# magnetorquer_board_f1.net
KiCad netlist of a schematic drawn in EAGLE
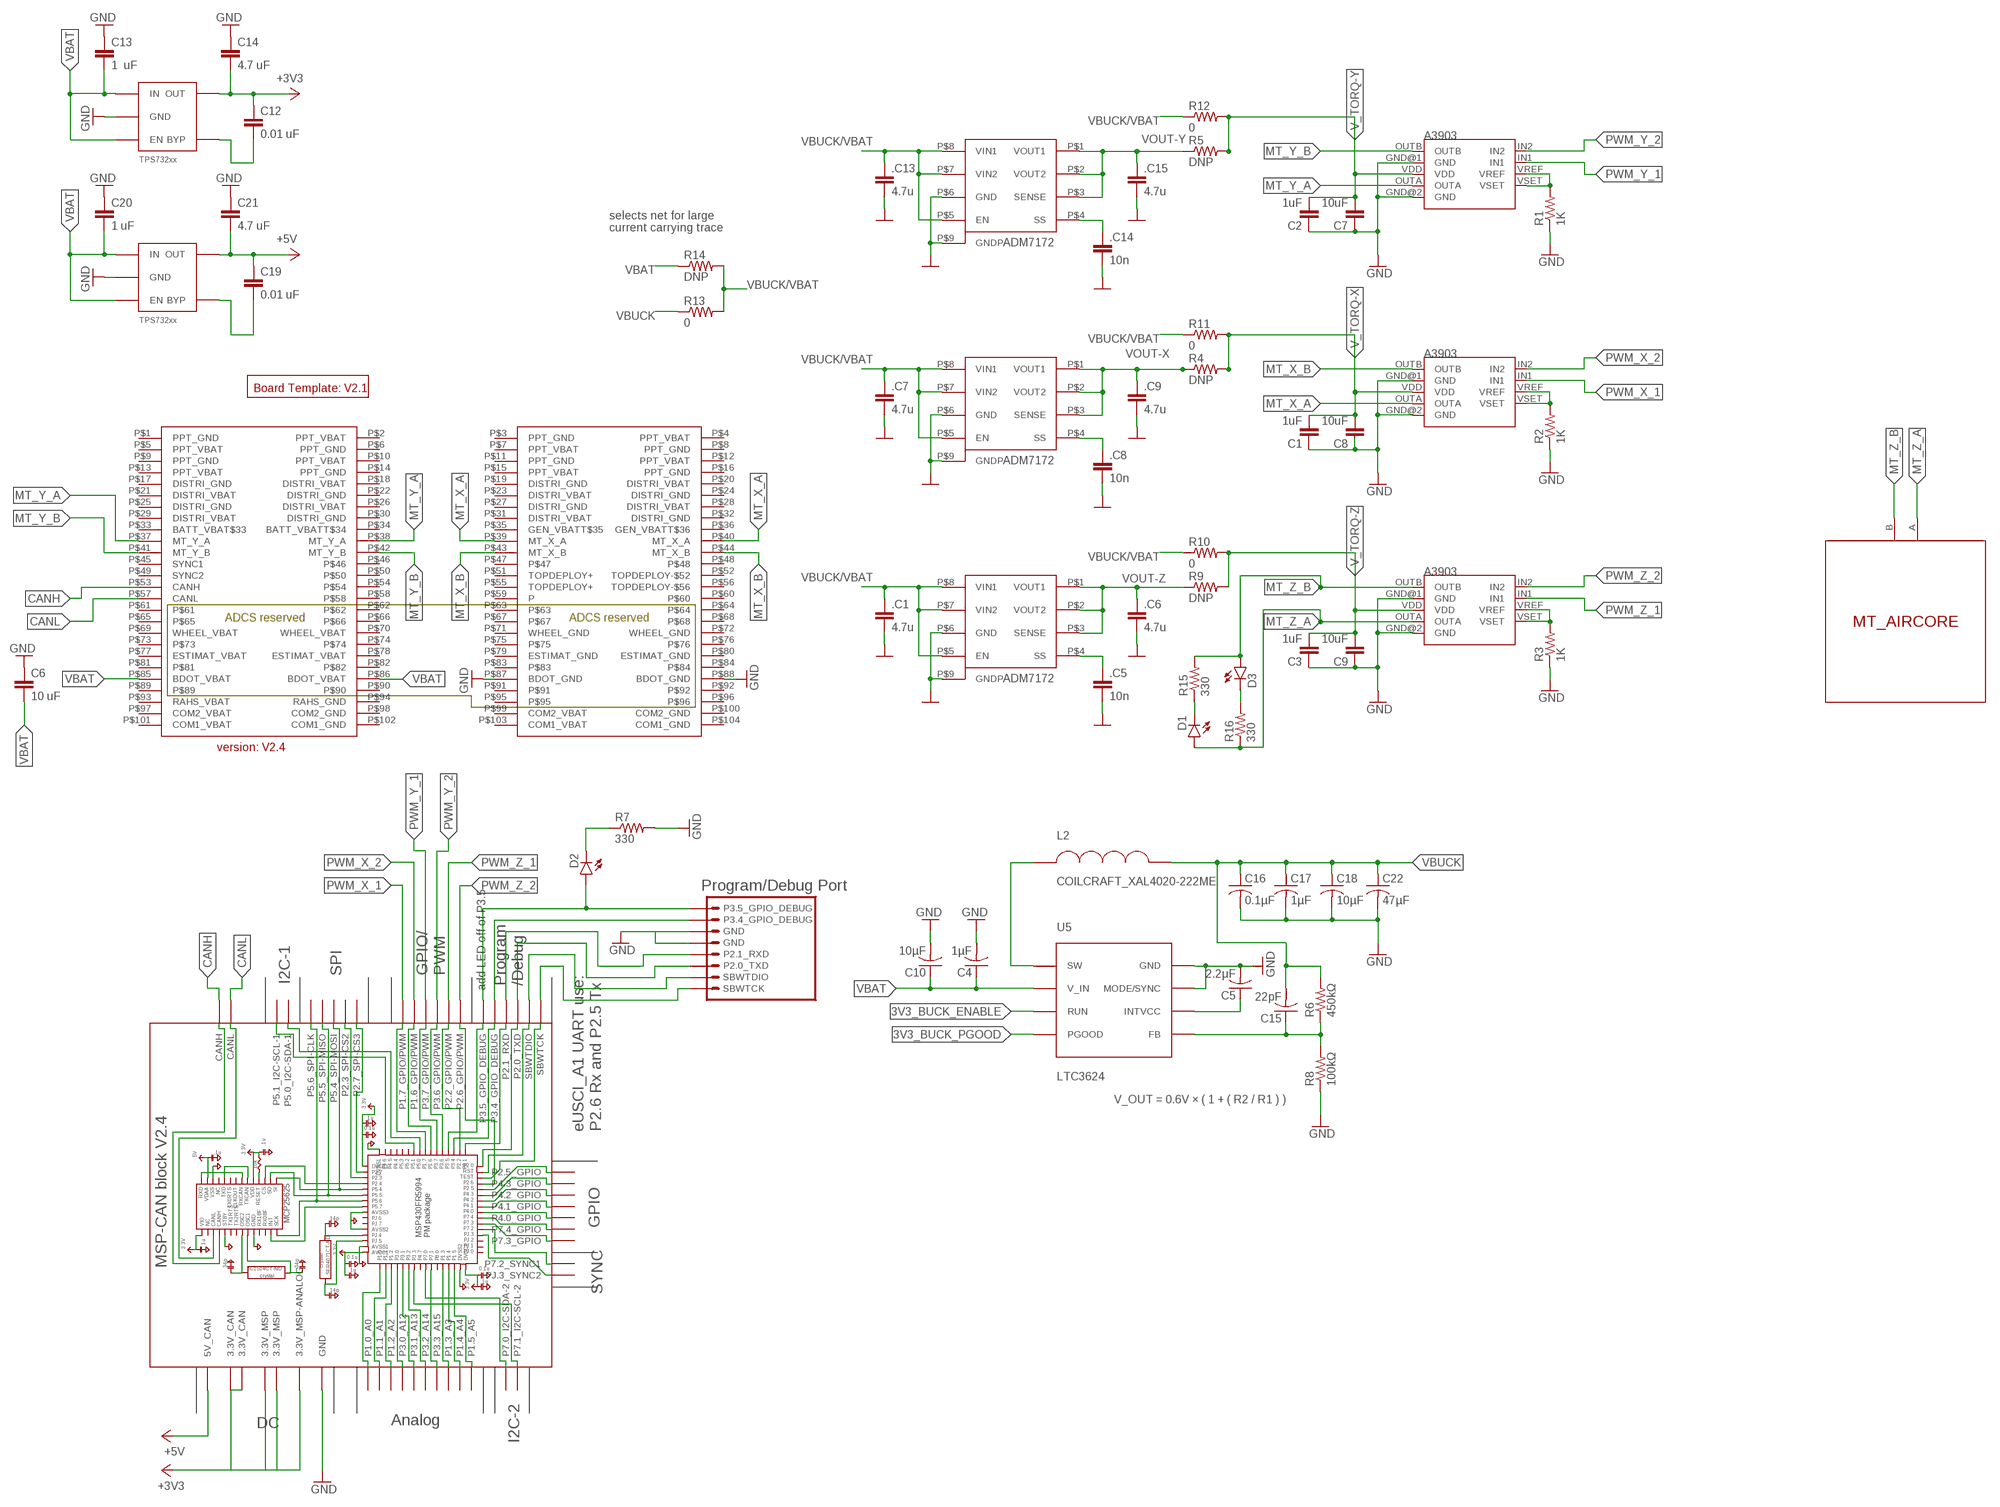
[diagram p0: schematic, sheet 1]

(export (version "E")
  (design (tool "Eeschema 10.0.6"))
  (components
    (comp (ref ".C1")
      (value "4.7u")
      (footprint "eagle-import:1206")
      (libsource (lib "eagle-import") (part "CAP1206"))
    )
    (comp (ref ".C5")
      (value "10n")
      (footprint "eagle-import:0805")
      (libsource (lib "eagle-import") (part "CAP0805"))
    )
    (comp (ref ".C6")
      (value "4.7u")
      (footprint "eagle-import:1206")
      (libsource (lib "eagle-import") (part "CAP1206"))
    )
    (comp (ref ".C7")
      (value "4.7u")
      (footprint "eagle-import:1206")
      (libsource (lib "eagle-import") (part "CAP1206"))
    )
    (comp (ref ".C8")
      (value "10n")
      (footprint "eagle-import:0805")
      (libsource (lib "eagle-import") (part "CAP0805"))
    )
    (comp (ref ".C9")
      (value "4.7u")
      (footprint "eagle-import:1206")
      (libsource (lib "eagle-import") (part "CAP1206"))
    )
    (comp (ref ".C13")
      (value "4.7u")
      (footprint "eagle-import:1206")
      (libsource (lib "eagle-import") (part "CAP1206"))
    )
    (comp (ref ".C14")
      (value "10n")
      (footprint "eagle-import:0805")
      (libsource (lib "eagle-import") (part "CAP0805"))
    )
    (comp (ref ".C15")
      (value "4.7u")
      (footprint "eagle-import:1206")
      (libsource (lib "eagle-import") (part "CAP1206"))
    )
    (comp (ref "C1")
      (value "1uF")
      (footprint "eagle-import:0805")
      (libsource (lib "eagle-import") (part "CAPACITOR0805"))
    )
    (comp (ref "C2")
      (value "1uF")
      (footprint "eagle-import:0805")
      (libsource (lib "eagle-import") (part "CAPACITOR0805"))
    )
    (comp (ref "C3")
      (value "1uF")
      (footprint "eagle-import:0805")
      (libsource (lib "eagle-import") (part "CAPACITOR0805"))
    )
    (comp (ref "C4")
      (value "1µF")
      (footprint "eagle-import:C0805")
      (libsource (lib "eagle-import") (part "C-USC0805"))
    )
    (comp (ref "C5")
      (value "2.2μF")
      (footprint "eagle-import:C0805")
      (libsource (lib "eagle-import") (part "C-USC0805"))
    )
    (comp (ref "C6")
      (value "10 uF")
      (footprint "eagle-import:0805")
      (libsource (lib "eagle-import") (part "CAPACITOR0805"))
    )
    (comp (ref "C7")
      (value "10uF")
      (footprint "eagle-import:0805")
      (libsource (lib "eagle-import") (part "CAPACITOR0805"))
    )
    (comp (ref "C8")
      (value "10uF")
      (footprint "eagle-import:0805")
      (libsource (lib "eagle-import") (part "CAPACITOR0805"))
    )
    (comp (ref "C9")
      (value "10uF")
      (footprint "eagle-import:0805")
      (libsource (lib "eagle-import") (part "CAPACITOR0805"))
    )
    (comp (ref "C10")
      (value "10µF")
      (footprint "eagle-import:C0805")
      (libsource (lib "eagle-import") (part "C-USC0805"))
    )
    (comp (ref "C12")
      (value "0.01 uF")
      (footprint "eagle-import:0805")
      (libsource (lib "eagle-import") (part "CAPACITOR0805"))
    )
    (comp (ref "C13")
      (value "1 uF")
      (footprint "eagle-import:0805")
      (libsource (lib "eagle-import") (part "CAPACITOR0805"))
    )
    (comp (ref "C14")
      (value "4.7 uF")
      (footprint "eagle-import:0805")
      (libsource (lib "eagle-import") (part "CAPACITOR0805"))
    )
    (comp (ref "C15")
      (value "22pF")
      (footprint "eagle-import:C0805")
      (libsource (lib "eagle-import") (part "C-USC0805"))
    )
    (comp (ref "C16")
      (value "0.1µF")
      (footprint "eagle-import:C1206")
      (libsource (lib "eagle-import") (part "C-USC1206"))
    )
    (comp (ref "C17")
      (value "1µF")
      (footprint "eagle-import:C0805")
      (libsource (lib "eagle-import") (part "C-USC0805"))
    )
    (comp (ref "C18")
      (value "10µF")
      (footprint "eagle-import:C0805")
      (libsource (lib "eagle-import") (part "C-USC0805"))
    )
    (comp (ref "C19")
      (value "0.01 uF")
      (footprint "eagle-import:0805")
      (libsource (lib "eagle-import") (part "CAPACITOR0805"))
    )
    (comp (ref "C20")
      (value "1 uF")
      (footprint "eagle-import:0805")
      (libsource (lib "eagle-import") (part "CAPACITOR0805"))
    )
    (comp (ref "C21")
      (value "4.7 uF")
      (footprint "eagle-import:0805")
      (libsource (lib "eagle-import") (part "CAPACITOR0805"))
    )
    (comp (ref "C22")
      (value "47µF")
      (footprint "eagle-import:C0805")
      (libsource (lib "eagle-import") (part "C-USC0805"))
    )
    (comp (ref "D1")
      (value "LED")
      (footprint "eagle-import:LED-1206")
      (libsource (lib "eagle-import") (part "LED"))
    )
    (comp (ref "D2")
      (value "LED")
      (footprint "eagle-import:LED-1206")
      (libsource (lib "eagle-import") (part "LED"))
    )
    (comp (ref "D3")
      (value "LED")
      (footprint "eagle-import:LED-1206")
      (libsource (lib "eagle-import") (part "LED"))
    )
    (comp (ref "L2")
      (value "COILCRAFT_XAL4020-222ME")
      (footprint "eagle-import:COILCRAFT_XAL4020")
      (libsource (lib "eagle-import") (part "COILCRAFT_XAL4020-222ME"))
    )
    (comp (ref "LDO_3V1")
      (value "TPS732XX")
      (footprint "eagle-import:SOT-23-5")
      (libsource (lib "eagle-import") (part "TPS732XX"))
    )
    (comp (ref "LDO_5V1")
      (value "TPS732XX")
      (footprint "eagle-import:SOT-23-5")
      (libsource (lib "eagle-import") (part "TPS732XX"))
    )
    (comp (ref "R1")
      (value "1K")
      (footprint "eagle-import:R0603")
      (libsource (lib "eagle-import") (part "R-US_R0603"))
    )
    (comp (ref "R2")
      (value "1K")
      (footprint "eagle-import:R0603")
      (libsource (lib "eagle-import") (part "R-US_R0603"))
    )
    (comp (ref "R3")
      (value "1K")
      (footprint "eagle-import:R0603")
      (libsource (lib "eagle-import") (part "R-US_R0603"))
    )
    (comp (ref "R4")
      (value "DNP")
      (footprint "eagle-import:0805")
      (libsource (lib "eagle-import") (part "RESISTOR0805"))
    )
    (comp (ref "R5")
      (value "DNP")
      (footprint "eagle-import:0805")
      (libsource (lib "eagle-import") (part "RESISTOR0805"))
    )
    (comp (ref "R6")
      (value "450kΩ")
      (footprint "eagle-import:R0805")
      (libsource (lib "eagle-import") (part "R-US_R0805"))
    )
    (comp (ref "R7")
      (value "330")
      (footprint "eagle-import:0805")
      (libsource (lib "eagle-import") (part "RESISTOR0805"))
    )
    (comp (ref "R8")
      (value "100kΩ")
      (footprint "eagle-import:R0805")
      (libsource (lib "eagle-import") (part "R-US_R0805"))
    )
    (comp (ref "R9")
      (value "DNP")
      (footprint "eagle-import:0805")
      (libsource (lib "eagle-import") (part "RESISTOR0805"))
    )
    (comp (ref "R10")
      (value "0")
      (footprint "eagle-import:0805")
      (libsource (lib "eagle-import") (part "RESISTOR0805"))
    )
    (comp (ref "R11")
      (value "0")
      (footprint "eagle-import:0805")
      (libsource (lib "eagle-import") (part "RESISTOR0805"))
    )
    (comp (ref "R12")
      (value "0")
      (footprint "eagle-import:0805")
      (libsource (lib "eagle-import") (part "RESISTOR0805"))
    )
    (comp (ref "R13")
      (value "0")
      (footprint "eagle-import:R2010")
      (libsource (lib "eagle-import") (part "RESISTOR2010"))
    )
    (comp (ref "R14")
      (value "DNP")
      (footprint "eagle-import:R2010")
      (libsource (lib "eagle-import") (part "RESISTOR2010"))
    )
    (comp (ref "R15")
      (value "330")
      (footprint "eagle-import:0805")
      (libsource (lib "eagle-import") (part "RESISTOR0805"))
    )
    (comp (ref "R16")
      (value "330")
      (footprint "eagle-import:0805")
      (libsource (lib "eagle-import") (part "RESISTOR0805"))
    )
    (comp (ref "U$1")
      (value "PC104_CONNECTOR")
      (footprint "eagle-import:PC104_CONNECTOR")
      (libsource (lib "eagle-import") (part "PC104_CONNECTOR"))
    )
    (comp (ref "U$2")
      (value "BOARD_TEMPLATE1")
      (footprint "eagle-import:BOARD_TEMPLATE")
      (libsource (lib "eagle-import") (part "BOARD_TEMPLATE1"))
    )
    (comp (ref "U$3")
      (value "MT_AIRCORE")
      (footprint "eagle-import:MT_AIRCORE")
      (libsource (lib "eagle-import") (part "MT_AIRCORE"))
    )
    (comp (ref "U$4")
      (value "ANALOG_LDO_ADM7172")
      (footprint "eagle-import:8-LFCSP")
      (libsource (lib "eagle-import") (part "ANALOG_LDO_ADM7172"))
    )
    (comp (ref "U$5")
      (value "ANALOG_LDO_ADM7172")
      (footprint "eagle-import:8-LFCSP")
      (libsource (lib "eagle-import") (part "ANALOG_LDO_ADM7172"))
    )
    (comp (ref "U$7")
      (value "MSP-CAN_BLOCK")
      (footprint "eagle-import:MSP-CAN_BLOCK")
      (libsource (lib "eagle-import") (part "MSP-CAN_BLOCK"))
    )
    (comp (ref "U$8")
      (value "PROGRAM/DEBUG_PORT")
      (footprint "eagle-import:1X08_CONNECTOR")
      (libsource (lib "eagle-import") (part "PROGRAM/DEBUG_PORT"))
    )
    (comp (ref "U$9")
      (value "ANALOG_LDO_ADM7172")
      (footprint "eagle-import:8-LFCSP")
      (libsource (lib "eagle-import") (part "ANALOG_LDO_ADM7172"))
    )
    (comp (ref "U1")
      (value "A3903")
      (footprint "eagle-import:DFN-8EE")
      (libsource (lib "eagle-import") (part "A3903"))
    )
    (comp (ref "U2")
      (value "A3903")
      (footprint "eagle-import:DFN-8EE")
      (libsource (lib "eagle-import") (part "A3903"))
    )
    (comp (ref "U3")
      (value "A3903")
      (footprint "eagle-import:DFN-8EE")
      (libsource (lib "eagle-import") (part "A3903"))
    )
    (comp (ref "U5")
      (value "LTC3624")
      (footprint "eagle-import:LTC3624")
      (libsource (lib "eagle-import") (part "LTC3624"))
    )
  )
  (nets
    (net (code "1") (name "+3V3") (class "Default")
      (node (ref "C12") (pin "1") (pinfunction "1_1") (pintype "passive"))
      (node (ref "C14") (pin "2") (pinfunction "2_2") (pintype "passive"))
      (node (ref "LDO_3V1") (pin "P$5") (pinfunction "OUT_P$5") (pintype "bidirectional"))
      (node (ref "U$7") (pin "3.3V@CAN1") (pinfunction "3.3V_CAN_3.3V@CAN1") (pintype "bidirectional"))
      (node (ref "U$7") (pin "3.3V@CAN2") (pinfunction "3.3V_CAN_3.3V@CAN2") (pintype "bidirectional"))
      (node (ref "U$7") (pin "3.3V@MSP1") (pinfunction "3.3V_MSP_3.3V@MSP1") (pintype "bidirectional"))
      (node (ref "U$7") (pin "3.3V@MSP2") (pinfunction "3.3V_MSP_3.3V@MSP2") (pintype "bidirectional"))
      (node (ref "U$7") (pin "3.3V_ANALOG@MSP2") (pinfunction "3.3V_MSP-ANALOG_3.3V_ANALOG@MSP2") (pintype "bidirectional"))
    )
    (net (code "2") (name "+5V") (class "Default")
      (node (ref "C19") (pin "1") (pinfunction "1_1") (pintype "passive"))
      (node (ref "C21") (pin "2") (pinfunction "2_2") (pintype "passive"))
      (node (ref "LDO_5V1") (pin "P$5") (pinfunction "OUT_P$5") (pintype "bidirectional"))
      (node (ref "U$7") (pin "5V") (pinfunction "5V_CAN_5V") (pintype "bidirectional"))
    )
    (net (code "3") (name "/VBUCK{slash}VBAT") (class "Default")
      (node (ref ".C1") (pin "1") (pinfunction "1_1") (pintype "passive"))
      (node (ref ".C13") (pin "1") (pinfunction "1_1") (pintype "passive"))
      (node (ref ".C7") (pin "1") (pinfunction "1_1") (pintype "passive"))
      (node (ref "R10") (pin "1") (pinfunction "1_1") (pintype "passive"))
      (node (ref "R11") (pin "1") (pinfunction "1_1") (pintype "passive"))
      (node (ref "R12") (pin "1") (pinfunction "1_1") (pintype "passive"))
      (node (ref "R13") (pin "2") (pinfunction "2_2") (pintype "passive"))
      (node (ref "R14") (pin "2") (pinfunction "2_2") (pintype "passive"))
      (node (ref "U$4") (pin "P$5") (pinfunction "EN_P$5") (pintype "bidirectional"))
      (node (ref "U$4") (pin "P$7") (pinfunction "VIN2_P$7") (pintype "bidirectional"))
      (node (ref "U$4") (pin "P$8") (pinfunction "VIN1_P$8") (pintype "bidirectional"))
      (node (ref "U$5") (pin "P$5") (pinfunction "EN_P$5") (pintype "bidirectional"))
      (node (ref "U$5") (pin "P$7") (pinfunction "VIN2_P$7") (pintype "bidirectional"))
      (node (ref "U$5") (pin "P$8") (pinfunction "VIN1_P$8") (pintype "bidirectional"))
      (node (ref "U$9") (pin "P$5") (pinfunction "EN_P$5") (pintype "bidirectional"))
      (node (ref "U$9") (pin "P$7") (pinfunction "VIN2_P$7") (pintype "bidirectional"))
      (node (ref "U$9") (pin "P$8") (pinfunction "VIN1_P$8") (pintype "bidirectional"))
    )
    (net (code "4") (name "/VOUT-X") (class "Default")
      (node (ref ".C9") (pin "1") (pinfunction "1_1") (pintype "passive"))
      (node (ref "R4") (pin "1") (pinfunction "1_1") (pintype "passive"))
      (node (ref "U$5") (pin "P$1") (pinfunction "VOUT1_P$1") (pintype "bidirectional"))
      (node (ref "U$5") (pin "P$2") (pinfunction "VOUT2_P$2") (pintype "bidirectional"))
      (node (ref "U$5") (pin "P$3") (pinfunction "SENSE_P$3") (pintype "bidirectional"))
    )
    (net (code "5") (name "/VOUT-Y") (class "Default")
      (node (ref ".C15") (pin "1") (pinfunction "1_1") (pintype "passive"))
      (node (ref "R5") (pin "1") (pinfunction "1_1") (pintype "passive"))
      (node (ref "U$9") (pin "P$1") (pinfunction "VOUT1_P$1") (pintype "bidirectional"))
      (node (ref "U$9") (pin "P$2") (pinfunction "VOUT2_P$2") (pintype "bidirectional"))
      (node (ref "U$9") (pin "P$3") (pinfunction "SENSE_P$3") (pintype "bidirectional"))
    )
    (net (code "6") (name "/VOUT-Z") (class "Default")
      (node (ref ".C6") (pin "1") (pinfunction "1_1") (pintype "passive"))
      (node (ref "R9") (pin "1") (pinfunction "1_1") (pintype "passive"))
      (node (ref "U$4") (pin "P$1") (pinfunction "VOUT1_P$1") (pintype "bidirectional"))
      (node (ref "U$4") (pin "P$2") (pinfunction "VOUT2_P$2") (pintype "bidirectional"))
      (node (ref "U$4") (pin "P$3") (pinfunction "SENSE_P$3") (pintype "bidirectional"))
    )
    (net (code "7") (name "3V3_BUCK_ENABLE") (class "Default")
      (node (ref "U5") (pin "RUN") (pinfunction "RUN_RUN") (pintype "bidirectional"))
    )
    (net (code "8") (name "3V3_BUCK_PGOOD") (class "Default")
      (node (ref "U5") (pin "PGOOD") (pinfunction "PGOOD_PGOOD") (pintype "bidirectional"))
    )
    (net (code "9") (name "CANH") (class "Default")
      (node (ref "U$1") (pin "P$53") (pinfunction "CANH_P$53") (pintype "bidirectional"))
      (node (ref "U$7") (pin "CANH") (pinfunction "CANH_CANH") (pintype "bidirectional"))
    )
    (net (code "10") (name "CANL") (class "Default")
      (node (ref "U$1") (pin "P$57") (pinfunction "CANL_P$57") (pintype "bidirectional"))
      (node (ref "U$7") (pin "CANL") (pinfunction "CANL_CANL") (pintype "bidirectional"))
    )
    (net (code "11") (name "DGND") (class "Default")
      (node (ref ".C1") (pin "2") (pinfunction "2_2") (pintype "passive"))
      (node (ref ".C13") (pin "2") (pinfunction "2_2") (pintype "passive"))
      (node (ref ".C14") (pin "2") (pinfunction "2_2") (pintype "passive"))
      (node (ref ".C15") (pin "2") (pinfunction "2_2") (pintype "passive"))
      (node (ref ".C5") (pin "2") (pinfunction "2_2") (pintype "passive"))
      (node (ref ".C6") (pin "2") (pinfunction "2_2") (pintype "passive"))
      (node (ref ".C7") (pin "2") (pinfunction "2_2") (pintype "passive"))
      (node (ref ".C8") (pin "2") (pinfunction "2_2") (pintype "passive"))
      (node (ref ".C9") (pin "2") (pinfunction "2_2") (pintype "passive"))
      (node (ref "C1") (pin "1") (pinfunction "1_1") (pintype "passive"))
      (node (ref "C10") (pin "2") (pinfunction "2_2") (pintype "passive"))
      (node (ref "C13") (pin "1") (pinfunction "1_1") (pintype "passive"))
      (node (ref "C14") (pin "1") (pinfunction "1_1") (pintype "passive"))
      (node (ref "C16") (pin "2") (pinfunction "2_2") (pintype "passive"))
      (node (ref "C17") (pin "2") (pinfunction "2_2") (pintype "passive"))
      (node (ref "C18") (pin "2") (pinfunction "2_2") (pintype "passive"))
      (node (ref "C2") (pin "1") (pinfunction "1_1") (pintype "passive"))
      (node (ref "C20") (pin "1") (pinfunction "1_1") (pintype "passive"))
      (node (ref "C21") (pin "1") (pinfunction "1_1") (pintype "passive"))
      (node (ref "C22") (pin "2") (pinfunction "2_2") (pintype "passive"))
      (node (ref "C3") (pin "1") (pinfunction "1_1") (pintype "passive"))
      (node (ref "C4") (pin "2") (pinfunction "2_2") (pintype "passive"))
      (node (ref "C5") (pin "2") (pinfunction "2_2") (pintype "passive"))
      (node (ref "C6") (pin "1") (pinfunction "1_1") (pintype "passive"))
      (node (ref "C7") (pin "1") (pinfunction "1_1") (pintype "passive"))
      (node (ref "C8") (pin "1") (pinfunction "1_1") (pintype "passive"))
      (node (ref "C9") (pin "1") (pinfunction "1_1") (pintype "passive"))
      (node (ref "LDO_3V1") (pin "P$2") (pinfunction "GND_P$2") (pintype "bidirectional"))
      (node (ref "LDO_5V1") (pin "P$2") (pinfunction "GND_P$2") (pintype "bidirectional"))
      (node (ref "R1") (pin "1") (pinfunction "1_1") (pintype "passive"))
      (node (ref "R2") (pin "1") (pinfunction "1_1") (pintype "passive"))
      (node (ref "R3") (pin "1") (pinfunction "1_1") (pintype "passive"))
      (node (ref "R7") (pin "2") (pinfunction "2_2") (pintype "passive"))
      (node (ref "R8") (pin "1") (pinfunction "1_1") (pintype "passive"))
      (node (ref "U$1") (pin "P$87") (pinfunction "BDOT_GND_P$87") (pintype "bidirectional"))
      (node (ref "U$1") (pin "P$88") (pinfunction "BDOT_GND_P$88") (pintype "bidirectional"))
      (node (ref "U$4") (pin "P$6") (pinfunction "GND_P$6") (pintype "bidirectional"))
      (node (ref "U$4") (pin "P$9") (pinfunction "GNDP_P$9") (pintype "bidirectional"))
      (node (ref "U$5") (pin "P$6") (pinfunction "GND_P$6") (pintype "bidirectional"))
      (node (ref "U$5") (pin "P$9") (pinfunction "GNDP_P$9") (pintype "bidirectional"))
      (node (ref "U$7") (pin "GND@1") (pinfunction "GND_GND@1") (pintype "bidirectional"))
      (node (ref "U$7") (pin "GND@10") (pinfunction "GND_GND@10") (pintype "bidirectional"))
      (node (ref "U$7") (pin "GND@11") (pinfunction "GND_GND@11") (pintype "bidirectional"))
      (node (ref "U$7") (pin "GND@12") (pinfunction "GND_GND@12") (pintype "bidirectional"))
      (node (ref "U$7") (pin "GND@13") (pinfunction "GND_GND@13") (pintype "bidirectional"))
      (node (ref "U$7") (pin "GND@14") (pinfunction "GND_GND@14") (pintype "bidirectional"))
      (node (ref "U$7") (pin "GND@15") (pinfunction "GND_GND@15") (pintype "bidirectional"))
      (node (ref "U$7") (pin "GND@16") (pinfunction "GND_GND@16") (pintype "bidirectional"))
      (node (ref "U$7") (pin "GND@17") (pinfunction "GND_GND@17") (pintype "bidirectional"))
      (node (ref "U$7") (pin "GND@2") (pinfunction "GND_GND@2") (pintype "bidirectional"))
      (node (ref "U$7") (pin "GND@26") (pinfunction "GND_GND@26") (pintype "bidirectional"))
      (node (ref "U$7") (pin "GND@3") (pinfunction "GND_GND@3") (pintype "bidirectional"))
      (node (ref "U$7") (pin "GND@4") (pinfunction "GND_GND@4") (pintype "bidirectional"))
      (node (ref "U$7") (pin "GND@5") (pinfunction "GND_GND@5") (pintype "bidirectional"))
      (node (ref "U$7") (pin "GND@7") (pinfunction "GND_GND@7") (pintype "bidirectional"))
      (node (ref "U$7") (pin "GND@8") (pinfunction "GND_GND@8") (pintype "bidirectional"))
      (node (ref "U$7") (pin "GND@9") (pinfunction "GND_GND@9") (pintype "bidirectional"))
      (node (ref "U$8") (pin "5") (pinfunction "GND_5") (pintype "bidirectional"))
      (node (ref "U$8") (pin "6") (pinfunction "GND_6") (pintype "bidirectional"))
      (node (ref "U$9") (pin "P$6") (pinfunction "GND_P$6") (pintype "bidirectional"))
      (node (ref "U$9") (pin "P$9") (pinfunction "GNDP_P$9") (pintype "bidirectional"))
      (node (ref "U1") (pin "GND@1") (pinfunction "GND_GND@1") (pintype "power_in"))
      (node (ref "U1") (pin "GND@2") (pinfunction "GND_GND@2") (pintype "power_in"))
      (node (ref "U2") (pin "GND@1") (pinfunction "GND_GND@1") (pintype "power_in"))
      (node (ref "U2") (pin "GND@2") (pinfunction "GND_GND@2") (pintype "power_in"))
      (node (ref "U3") (pin "GND@1") (pinfunction "GND_GND@1") (pintype "power_in"))
      (node (ref "U3") (pin "GND@2") (pinfunction "GND_GND@2") (pintype "power_in"))
      (node (ref "U5") (pin "GND@1") (pinfunction "GND_GND@1") (pintype "bidirectional"))
      (node (ref "U5") (pin "GND@PAD") (pinfunction "GND_GND@PAD") (pintype "bidirectional"))
      (node (ref "U5") (pin "MODE/SYNC") (pinfunction "MODE/SYNC_MODE/SYNC") (pintype "bidirectional"))
    )
    (net (code "12") (name "MT_X_A") (class "Default")
      (node (ref "U$1") (pin "P$39") (pinfunction "MT_X_A_P$39") (pintype "bidirectional"))
      (node (ref "U$1") (pin "P$40") (pinfunction "MT_X_A_P$40") (pintype "bidirectional"))
      (node (ref "U2") (pin "OUTA") (pinfunction "OUTA_OUTA") (pintype "output"))
    )
    (net (code "13") (name "MT_X_B") (class "Default")
      (node (ref "U$1") (pin "P$43") (pinfunction "MT_X_B_P$43") (pintype "bidirectional"))
      (node (ref "U$1") (pin "P$44") (pinfunction "MT_X_B_P$44") (pintype "bidirectional"))
      (node (ref "U2") (pin "OUTB") (pinfunction "OUTB_OUTB") (pintype "output"))
    )
    (net (code "14") (name "MT_Y_A") (class "Default")
      (node (ref "U$1") (pin "P$37") (pinfunction "MT_Y_A_P$37") (pintype "bidirectional"))
      (node (ref "U$1") (pin "P$38") (pinfunction "MT_Y_A_P$38") (pintype "bidirectional"))
      (node (ref "U1") (pin "OUTA") (pinfunction "OUTA_OUTA") (pintype "output"))
    )
    (net (code "15") (name "MT_Y_B") (class "Default")
      (node (ref "U$1") (pin "P$41") (pinfunction "MT_Y_B_P$41") (pintype "bidirectional"))
      (node (ref "U$1") (pin "P$42") (pinfunction "MT_Y_B_P$42") (pintype "bidirectional"))
      (node (ref "U1") (pin "OUTB") (pinfunction "OUTB_OUTB") (pintype "output"))
    )
    (net (code "16") (name "MT_Z_A") (class "Default")
      (node (ref "D1") (pin "A") (pinfunction "A_A") (pintype "passive"))
      (node (ref "R16") (pin "1") (pinfunction "1_1") (pintype "passive"))
      (node (ref "U$3") (pin "A") (pinfunction "A_A") (pintype "bidirectional"))
      (node (ref "U3") (pin "OUTA") (pinfunction "OUTA_OUTA") (pintype "output"))
    )
    (net (code "17") (name "MT_Z_B") (class "Default")
      (node (ref "D3") (pin "A") (pinfunction "A_A") (pintype "passive"))
      (node (ref "R15") (pin "2") (pinfunction "2_2") (pintype "passive"))
      (node (ref "U$3") (pin "B") (pinfunction "B_B") (pintype "bidirectional"))
      (node (ref "U3") (pin "OUTB") (pinfunction "OUTB_OUTB") (pintype "output"))
    )
    (net (code "18") (name "Net-(C5-Pad1)") (class "Default")
      (node (ref "C5") (pin "1") (pinfunction "1_1") (pintype "passive"))
      (node (ref "U5") (pin "INTVCC") (pinfunction "INTVCC_INTVCC") (pintype "bidirectional"))
    )
    (net (code "19") (name "Net-(C15-Pad1)") (class "Default")
      (node (ref "C15") (pin "1") (pinfunction "1_1") (pintype "passive"))
      (node (ref "R6") (pin "1") (pinfunction "1_1") (pintype "passive"))
      (node (ref "R8") (pin "2") (pinfunction "2_2") (pintype "passive"))
      (node (ref "U5") (pin "FB") (pinfunction "FB_FB") (pintype "bidirectional"))
    )
    (net (code "20") (name "Net-(D1-PadC)") (class "Default")
      (node (ref "D1") (pin "C") (pinfunction "C_C") (pintype "passive"))
      (node (ref "R15") (pin "1") (pinfunction "1_1") (pintype "passive"))
    )
    (net (code "21") (name "Net-(D2-PadC)") (class "Default")
      (node (ref "D2") (pin "C") (pinfunction "C_C") (pintype "passive"))
      (node (ref "R7") (pin "1") (pinfunction "1_1") (pintype "passive"))
    )
    (net (code "22") (name "Net-(D3-PadC)") (class "Default")
      (node (ref "D3") (pin "C") (pinfunction "C_C") (pintype "passive"))
      (node (ref "R16") (pin "2") (pinfunction "2_2") (pintype "passive"))
    )
    (net (code "23") (name "Net-(L2-PadP$1)") (class "Default")
      (node (ref "L2") (pin "P$1") (pinfunction "P$1_P$1") (pintype "bidirectional"))
      (node (ref "U5") (pin "SW") (pinfunction "SW_SW") (pintype "bidirectional"))
    )
    (net (code "24") (name "Net-(LDO_3V1-BYP)") (class "Default")
      (node (ref "C12") (pin "2") (pinfunction "2_2") (pintype "passive"))
      (node (ref "LDO_3V1") (pin "P$4") (pinfunction "BYP_P$4") (pintype "bidirectional"))
    )
    (net (code "25") (name "Net-(LDO_5V1-BYP)") (class "Default")
      (node (ref "C19") (pin "2") (pinfunction "2_2") (pintype "passive"))
      (node (ref "LDO_5V1") (pin "P$4") (pinfunction "BYP_P$4") (pintype "bidirectional"))
    )
    (net (code "26") (name "Net-(R1-Pad2)") (class "Default")
      (node (ref "R1") (pin "2") (pinfunction "2_2") (pintype "passive"))
      (node (ref "U1") (pin "VREF") (pinfunction "VREF_VREF") (pintype "power_in"))
      (node (ref "U1") (pin "VSET") (pinfunction "VSET_VSET") (pintype "bidirectional"))
    )
    (net (code "27") (name "Net-(R2-Pad2)") (class "Default")
      (node (ref "R2") (pin "2") (pinfunction "2_2") (pintype "passive"))
      (node (ref "U2") (pin "VREF") (pinfunction "VREF_VREF") (pintype "power_in"))
      (node (ref "U2") (pin "VSET") (pinfunction "VSET_VSET") (pintype "bidirectional"))
    )
    (net (code "28") (name "Net-(R3-Pad2)") (class "Default")
      (node (ref "R3") (pin "2") (pinfunction "2_2") (pintype "passive"))
      (node (ref "U3") (pin "VREF") (pinfunction "VREF_VREF") (pintype "power_in"))
      (node (ref "U3") (pin "VSET") (pinfunction "VSET_VSET") (pintype "bidirectional"))
    )
    (net (code "29") (name "Net-(U$4-SS)") (class "Default")
      (node (ref ".C5") (pin "1") (pinfunction "1_1") (pintype "passive"))
      (node (ref "U$4") (pin "P$4") (pinfunction "SS_P$4") (pintype "bidirectional"))
    )
    (net (code "30") (name "Net-(U$5-SS)") (class "Default")
      (node (ref ".C8") (pin "1") (pinfunction "1_1") (pintype "passive"))
      (node (ref "U$5") (pin "P$4") (pinfunction "SS_P$4") (pintype "bidirectional"))
    )
    (net (code "31") (name "Net-(U$7-PadSBWTCK)") (class "Default")
      (node (ref "U$7") (pin "SBWTCK") (pinfunction "SBWTCK_SBWTCK") (pintype "bidirectional"))
      (node (ref "U$8") (pin "SBWTCK") (pinfunction "SBWTCK_SBWTCK") (pintype "bidirectional"))
    )
    (net (code "32") (name "Net-(U$8-P2.0_TXD)") (class "Default")
      (node (ref "U$7") (pin "P2.0_TXD") (pinfunction "P2.0_TXD_P2.0_TXD") (pintype "bidirectional"))
      (node (ref "U$8") (pin "3") (pinfunction "P2.0_TXD_3") (pintype "bidirectional"))
    )
    (net (code "33") (name "Net-(U$8-P2.1_RXD)") (class "Default")
      (node (ref "U$7") (pin "P2.1_RXD") (pinfunction "P2.1_RXD_P2.1_RXD") (pintype "bidirectional"))
      (node (ref "U$8") (pin "4") (pinfunction "P2.1_RXD_4") (pintype "bidirectional"))
    )
    (net (code "34") (name "Net-(U$8-P3.4_GPIO_DEBUG)") (class "Default")
      (node (ref "U$7") (pin "P3.4_GPIO_DEBUG") (pinfunction "P3.4_GPIO_DEBUG_P3.4_GPIO_DEBUG") (pintype "bidirectional"))
      (node (ref "U$8") (pin "7") (pinfunction "P3.4_GPIO_DEBUG_7") (pintype "bidirectional"))
    )
    (net (code "35") (name "Net-(U$8-P3.5_GPIO_DEBUG)") (class "Default")
      (node (ref "D2") (pin "A") (pinfunction "A_A") (pintype "passive"))
      (node (ref "U$7") (pin "P3.5_GPIO_DEBUG") (pinfunction "P3.5_GPIO_DEBUG_P3.5_GPIO_DEBUG") (pintype "bidirectional"))
      (node (ref "U$8") (pin "8") (pinfunction "P3.5_GPIO_DEBUG_8") (pintype "bidirectional"))
    )
    (net (code "36") (name "Net-(U$8-SBWTDIO)") (class "Default")
      (node (ref "U$7") (pin "SBWTDIO") (pinfunction "SBWTDIO_SBWTDIO") (pintype "bidirectional"))
      (node (ref "U$8") (pin "2") (pinfunction "SBWTDIO_2") (pintype "bidirectional"))
    )
    (net (code "37") (name "Net-(U$9-SS)") (class "Default")
      (node (ref ".C14") (pin "1") (pinfunction "1_1") (pintype "passive"))
      (node (ref "U$9") (pin "P$4") (pinfunction "SS_P$4") (pintype "bidirectional"))
    )
    (net (code "38") (name "PWM_X_1") (class "Default")
      (node (ref "U$7") (pin "P1.7_GPIO/PWM") (pinfunction "P1.7_GPIO/PWM_P1.7_GPIO/PWM") (pintype "bidirectional"))
      (node (ref "U2") (pin "IN1") (pinfunction "IN1_IN1") (pintype "input"))
    )
    (net (code "39") (name "PWM_X_2") (class "Default")
      (node (ref "U$7") (pin "P1.6_GPIO/PWM") (pinfunction "P1.6_GPIO/PWM_P1.6_GPIO/PWM") (pintype "bidirectional"))
      (node (ref "U2") (pin "IN2") (pinfunction "IN2_IN2") (pintype "input"))
    )
    (net (code "40") (name "PWM_Y_1") (class "Default")
      (node (ref "U$7") (pin "P3.7_GPIO/PWM") (pinfunction "P3.7_GPIO/PWM_P3.7_GPIO/PWM") (pintype "bidirectional"))
      (node (ref "U1") (pin "IN1") (pinfunction "IN1_IN1") (pintype "input"))
    )
    (net (code "41") (name "PWM_Y_2") (class "Default")
      (node (ref "U$7") (pin "P3.6_GPIO/PWM") (pinfunction "P3.6_GPIO/PWM_P3.6_GPIO/PWM") (pintype "bidirectional"))
      (node (ref "U1") (pin "IN2") (pinfunction "IN2_IN2") (pintype "input"))
    )
    (net (code "42") (name "PWM_Z_1") (class "Default")
      (node (ref "U$7") (pin "P2.2_GPIO/PWM") (pinfunction "P2.2_GPIO/PWM_P2.2_GPIO/PWM") (pintype "bidirectional"))
      (node (ref "U3") (pin "IN1") (pinfunction "IN1_IN1") (pintype "input"))
    )
    (net (code "43") (name "PWM_Z_2") (class "Default")
      (node (ref "U$7") (pin "P2.6_GPIO/PWM") (pinfunction "P2.6_GPIO/PWM_P2.6_GPIO/PWM") (pintype "bidirectional"))
      (node (ref "U3") (pin "IN2") (pinfunction "IN2_IN2") (pintype "input"))
    )
    (net (code "44") (name "VBAT") (class "Default")
      (node (ref "C10") (pin "1") (pinfunction "1_1") (pintype "passive"))
      (node (ref "C13") (pin "2") (pinfunction "2_2") (pintype "passive"))
      (node (ref "C20") (pin "2") (pinfunction "2_2") (pintype "passive"))
      (node (ref "C4") (pin "1") (pinfunction "1_1") (pintype "passive"))
      (node (ref "C6") (pin "2") (pinfunction "2_2") (pintype "passive"))
      (node (ref "LDO_3V1") (pin "P$1") (pinfunction "IN_P$1") (pintype "bidirectional"))
      (node (ref "LDO_3V1") (pin "P$3") (pinfunction "EN_P$3") (pintype "bidirectional"))
      (node (ref "LDO_5V1") (pin "P$1") (pinfunction "IN_P$1") (pintype "bidirectional"))
      (node (ref "LDO_5V1") (pin "P$3") (pinfunction "EN_P$3") (pintype "bidirectional"))
      (node (ref "R14") (pin "1") (pinfunction "1_1") (pintype "passive"))
      (node (ref "U$1") (pin "P$85") (pinfunction "BDOT_VBAT_P$85") (pintype "bidirectional"))
      (node (ref "U$1") (pin "P$86") (pinfunction "BDOT_VBAT_P$86") (pintype "bidirectional"))
      (node (ref "U5") (pin "V_IN") (pinfunction "V_IN_V_IN") (pintype "bidirectional"))
    )
    (net (code "45") (name "VBUCK") (class "Default")
      (node (ref "C15") (pin "2") (pinfunction "2_2") (pintype "passive"))
      (node (ref "C16") (pin "1") (pinfunction "1_1") (pintype "passive"))
      (node (ref "C17") (pin "1") (pinfunction "1_1") (pintype "passive"))
      (node (ref "C18") (pin "1") (pinfunction "1_1") (pintype "passive"))
      (node (ref "C22") (pin "1") (pinfunction "1_1") (pintype "passive"))
      (node (ref "L2") (pin "P$2") (pinfunction "P$2_P$2") (pintype "bidirectional"))
      (node (ref "R13") (pin "1") (pinfunction "1_1") (pintype "passive"))
      (node (ref "R6") (pin "2") (pinfunction "2_2") (pintype "passive"))
    )
    (net (code "46") (name "V_TORQ-X") (class "Default")
      (node (ref "C1") (pin "2") (pinfunction "2_2") (pintype "passive"))
      (node (ref "C8") (pin "2") (pinfunction "2_2") (pintype "passive"))
      (node (ref "R11") (pin "2") (pinfunction "2_2") (pintype "passive"))
      (node (ref "R4") (pin "2") (pinfunction "2_2") (pintype "passive"))
      (node (ref "U2") (pin "VDD") (pinfunction "VDD_VDD") (pintype "power_in"))
    )
    (net (code "47") (name "V_TORQ-Y") (class "Default")
      (node (ref "C2") (pin "2") (pinfunction "2_2") (pintype "passive"))
      (node (ref "C7") (pin "2") (pinfunction "2_2") (pintype "passive"))
      (node (ref "R12") (pin "2") (pinfunction "2_2") (pintype "passive"))
      (node (ref "R5") (pin "2") (pinfunction "2_2") (pintype "passive"))
      (node (ref "U1") (pin "VDD") (pinfunction "VDD_VDD") (pintype "power_in"))
    )
    (net (code "48") (name "V_TORQ-Z") (class "Default")
      (node (ref "C3") (pin "2") (pinfunction "2_2") (pintype "passive"))
      (node (ref "C9") (pin "2") (pinfunction "2_2") (pintype "passive"))
      (node (ref "R10") (pin "2") (pinfunction "2_2") (pintype "passive"))
      (node (ref "R9") (pin "2") (pinfunction "2_2") (pintype "passive"))
      (node (ref "U3") (pin "VDD") (pinfunction "VDD_VDD") (pintype "power_in"))
    )
    (net (code "49") (name "unconnected-(U$1-BATT_VBAT$33-PadP$33)") (class "Default")
      (node (ref "U$1") (pin "P$33") (pinfunction "BATT_VBAT$33_P$33") (pintype "bidirectional"))
    )
    (net (code "50") (name "unconnected-(U$1-BATT_VBATT$34-PadP$34)") (class "Default")
      (node (ref "U$1") (pin "P$34") (pinfunction "BATT_VBATT$34_P$34") (pintype "bidirectional"))
    )
    (net (code "51") (name "unconnected-(U$1-COM1_GND-PadP$102)") (class "Default")
      (node (ref "U$1") (pin "P$102") (pinfunction "COM1_GND_P$102") (pintype "bidirectional"))
    )
    (net (code "52") (name "unconnected-(U$1-COM1_GND-PadP$104)") (class "Default")
      (node (ref "U$1") (pin "P$104") (pinfunction "COM1_GND_P$104") (pintype "bidirectional"))
    )
    (net (code "53") (name "unconnected-(U$1-COM1_VBAT-PadP$101)") (class "Default")
      (node (ref "U$1") (pin "P$101") (pinfunction "COM1_VBAT_P$101") (pintype "bidirectional"))
    )
    (net (code "54") (name "unconnected-(U$1-COM1_VBAT-PadP$103)") (class "Default")
      (node (ref "U$1") (pin "P$103") (pinfunction "COM1_VBAT_P$103") (pintype "bidirectional"))
    )
    (net (code "55") (name "unconnected-(U$1-COM2_GND-PadP$98)") (class "Default")
      (node (ref "U$1") (pin "P$98") (pinfunction "COM2_GND_P$98") (pintype "bidirectional"))
    )
    (net (code "56") (name "unconnected-(U$1-COM2_GND-PadP$100)") (class "Default")
      (node (ref "U$1") (pin "P$100") (pinfunction "COM2_GND_P$100") (pintype "bidirectional"))
    )
    (net (code "57") (name "unconnected-(U$1-COM2_VBAT-PadP$97)") (class "Default")
      (node (ref "U$1") (pin "P$97") (pinfunction "COM2_VBAT_P$97") (pintype "bidirectional"))
    )
    (net (code "58") (name "unconnected-(U$1-COM2_VBAT-PadP$99)") (class "Default")
      (node (ref "U$1") (pin "P$99") (pinfunction "COM2_VBAT_P$99") (pintype "bidirectional"))
    )
    (net (code "59") (name "unconnected-(U$1-DISTRI_GND-PadP$17)") (class "Default")
      (node (ref "U$1") (pin "P$17") (pinfunction "DISTRI_GND_P$17") (pintype "bidirectional"))
    )
    (net (code "60") (name "unconnected-(U$1-DISTRI_GND-PadP$19)") (class "Default")
      (node (ref "U$1") (pin "P$19") (pinfunction "DISTRI_GND_P$19") (pintype "bidirectional"))
    )
    (net (code "61") (name "unconnected-(U$1-DISTRI_GND-PadP$22)") (class "Default")
      (node (ref "U$1") (pin "P$22") (pinfunction "DISTRI_GND_P$22") (pintype "bidirectional"))
    )
    (net (code "62") (name "unconnected-(U$1-DISTRI_GND-PadP$24)") (class "Default")
      (node (ref "U$1") (pin "P$24") (pinfunction "DISTRI_GND_P$24") (pintype "bidirectional"))
    )
    (net (code "63") (name "unconnected-(U$1-DISTRI_GND-PadP$25)") (class "Default")
      (node (ref "U$1") (pin "P$25") (pinfunction "DISTRI_GND_P$25") (pintype "bidirectional"))
    )
    (net (code "64") (name "unconnected-(U$1-DISTRI_GND-PadP$27)") (class "Default")
      (node (ref "U$1") (pin "P$27") (pinfunction "DISTRI_GND_P$27") (pintype "bidirectional"))
    )
    (net (code "65") (name "unconnected-(U$1-DISTRI_GND-PadP$30)") (class "Default")
      (node (ref "U$1") (pin "P$30") (pinfunction "DISTRI_GND_P$30") (pintype "bidirectional"))
    )
    (net (code "66") (name "unconnected-(U$1-DISTRI_GND-PadP$32)") (class "Default")
      (node (ref "U$1") (pin "P$32") (pinfunction "DISTRI_GND_P$32") (pintype "bidirectional"))
    )
    (net (code "67") (name "unconnected-(U$1-DISTRI_VBAT-PadP$18)") (class "Default")
      (node (ref "U$1") (pin "P$18") (pinfunction "DISTRI_VBAT_P$18") (pintype "bidirectional"))
    )
    (net (code "68") (name "unconnected-(U$1-DISTRI_VBAT-PadP$20)") (class "Default")
      (node (ref "U$1") (pin "P$20") (pinfunction "DISTRI_VBAT_P$20") (pintype "bidirectional"))
    )
    (net (code "69") (name "unconnected-(U$1-DISTRI_VBAT-PadP$21)") (class "Default")
      (node (ref "U$1") (pin "P$21") (pinfunction "DISTRI_VBAT_P$21") (pintype "bidirectional"))
    )
    (net (code "70") (name "unconnected-(U$1-DISTRI_VBAT-PadP$23)") (class "Default")
      (node (ref "U$1") (pin "P$23") (pinfunction "DISTRI_VBAT_P$23") (pintype "bidirectional"))
    )
    (net (code "71") (name "unconnected-(U$1-DISTRI_VBAT-PadP$26)") (class "Default")
      (node (ref "U$1") (pin "P$26") (pinfunction "DISTRI_VBAT_P$26") (pintype "bidirectional"))
    )
    (net (code "72") (name "unconnected-(U$1-DISTRI_VBAT-PadP$28)") (class "Default")
      (node (ref "U$1") (pin "P$28") (pinfunction "DISTRI_VBAT_P$28") (pintype "bidirectional"))
    )
    (net (code "73") (name "unconnected-(U$1-DISTRI_VBAT-PadP$29)") (class "Default")
      (node (ref "U$1") (pin "P$29") (pinfunction "DISTRI_VBAT_P$29") (pintype "bidirectional"))
    )
    (net (code "74") (name "unconnected-(U$1-DISTRI_VBAT-PadP$31)") (class "Default")
      (node (ref "U$1") (pin "P$31") (pinfunction "DISTRI_VBAT_P$31") (pintype "bidirectional"))
    )
    (net (code "75") (name "unconnected-(U$1-ESTIMAT_GND-PadP$79)") (class "Default")
      (node (ref "U$1") (pin "P$79") (pinfunction "ESTIMAT_GND_P$79") (pintype "bidirectional"))
    )
    (net (code "76") (name "unconnected-(U$1-ESTIMAT_GND-PadP$80)") (class "Default")
      (node (ref "U$1") (pin "P$80") (pinfunction "ESTIMAT_GND_P$80") (pintype "bidirectional"))
    )
    (net (code "77") (name "unconnected-(U$1-ESTIMAT_VBAT-PadP$77)") (class "Default")
      (node (ref "U$1") (pin "P$77") (pinfunction "ESTIMAT_VBAT_P$77") (pintype "bidirectional"))
    )
    (net (code "78") (name "unconnected-(U$1-ESTIMAT_VBAT-PadP$78)") (class "Default")
      (node (ref "U$1") (pin "P$78") (pinfunction "ESTIMAT_VBAT_P$78") (pintype "bidirectional"))
    )
    (net (code "79") (name "unconnected-(U$1-GEN_VBATT$35-PadP$35)") (class "Default")
      (node (ref "U$1") (pin "P$35") (pinfunction "GEN_VBATT$35_P$35") (pintype "bidirectional"))
    )
    (net (code "80") (name "unconnected-(U$1-GEN_VBATT$36-PadP$36)") (class "Default")
      (node (ref "U$1") (pin "P$36") (pinfunction "GEN_VBATT$36_P$36") (pintype "bidirectional"))
    )
    (net (code "81") (name "unconnected-(U$1-P-PadP$59)") (class "Default")
      (node (ref "U$1") (pin "P$59") (pinfunction "P_P$59") (pintype "bidirectional"))
    )
    (net (code "82") (name "unconnected-(U$1-PPT_GND-PadP$1)") (class "Default")
      (node (ref "U$1") (pin "P$1") (pinfunction "PPT_GND_P$1") (pintype "bidirectional"))
    )
    (net (code "83") (name "unconnected-(U$1-PPT_GND-PadP$3)") (class "Default")
      (node (ref "U$1") (pin "P$3") (pinfunction "PPT_GND_P$3") (pintype "bidirectional"))
    )
    (net (code "84") (name "unconnected-(U$1-PPT_GND-PadP$6)") (class "Default")
      (node (ref "U$1") (pin "P$6") (pinfunction "PPT_GND_P$6") (pintype "bidirectional"))
    )
    (net (code "85") (name "unconnected-(U$1-PPT_GND-PadP$8)") (class "Default")
      (node (ref "U$1") (pin "P$8") (pinfunction "PPT_GND_P$8") (pintype "bidirectional"))
    )
    (net (code "86") (name "unconnected-(U$1-PPT_GND-PadP$9)") (class "Default")
      (node (ref "U$1") (pin "P$9") (pinfunction "PPT_GND_P$9") (pintype "bidirectional"))
    )
    (net (code "87") (name "unconnected-(U$1-PPT_GND-PadP$11)") (class "Default")
      (node (ref "U$1") (pin "P$11") (pinfunction "PPT_GND_P$11") (pintype "bidirectional"))
    )
    (net (code "88") (name "unconnected-(U$1-PPT_GND-PadP$14)") (class "Default")
      (node (ref "U$1") (pin "P$14") (pinfunction "PPT_GND_P$14") (pintype "bidirectional"))
    )
    (net (code "89") (name "unconnected-(U$1-PPT_GND-PadP$16)") (class "Default")
      (node (ref "U$1") (pin "P$16") (pinfunction "PPT_GND_P$16") (pintype "bidirectional"))
    )
    (net (code "90") (name "unconnected-(U$1-PPT_VBAT-PadP$2)") (class "Default")
      (node (ref "U$1") (pin "P$2") (pinfunction "PPT_VBAT_P$2") (pintype "bidirectional"))
    )
    (net (code "91") (name "unconnected-(U$1-PPT_VBAT-PadP$4)") (class "Default")
      (node (ref "U$1") (pin "P$4") (pinfunction "PPT_VBAT_P$4") (pintype "bidirectional"))
    )
    (net (code "92") (name "unconnected-(U$1-PPT_VBAT-PadP$5)") (class "Default")
      (node (ref "U$1") (pin "P$5") (pinfunction "PPT_VBAT_P$5") (pintype "bidirectional"))
    )
    (net (code "93") (name "unconnected-(U$1-PPT_VBAT-PadP$7)") (class "Default")
      (node (ref "U$1") (pin "P$7") (pinfunction "PPT_VBAT_P$7") (pintype "bidirectional"))
    )
    (net (code "94") (name "unconnected-(U$1-PPT_VBAT-PadP$10)") (class "Default")
      (node (ref "U$1") (pin "P$10") (pinfunction "PPT_VBAT_P$10") (pintype "bidirectional"))
    )
    (net (code "95") (name "unconnected-(U$1-PPT_VBAT-PadP$12)") (class "Default")
      (node (ref "U$1") (pin "P$12") (pinfunction "PPT_VBAT_P$12") (pintype "bidirectional"))
    )
    (net (code "96") (name "unconnected-(U$1-PPT_VBAT-PadP$13)") (class "Default")
      (node (ref "U$1") (pin "P$13") (pinfunction "PPT_VBAT_P$13") (pintype "bidirectional"))
    )
    (net (code "97") (name "unconnected-(U$1-PPT_VBAT-PadP$15)") (class "Default")
      (node (ref "U$1") (pin "P$15") (pinfunction "PPT_VBAT_P$15") (pintype "bidirectional"))
    )
    (net (code "98") (name "unconnected-(U$1-PadP$46)") (class "Default")
      (node (ref "U$1") (pin "P$46") (pinfunction "P$46_P$46") (pintype "bidirectional"))
    )
    (net (code "99") (name "unconnected-(U$1-PadP$47)") (class "Default")
      (node (ref "U$1") (pin "P$47") (pinfunction "P$47_P$47") (pintype "bidirectional"))
    )
    (net (code "100") (name "unconnected-(U$1-PadP$48)") (class "Default")
      (node (ref "U$1") (pin "P$48") (pinfunction "P$48_P$48") (pintype "bidirectional"))
    )
    (net (code "101") (name "unconnected-(U$1-PadP$50)") (class "Default")
      (node (ref "U$1") (pin "P$50") (pinfunction "P$50_P$50") (pintype "bidirectional"))
    )
    (net (code "102") (name "unconnected-(U$1-PadP$54)") (class "Default")
      (node (ref "U$1") (pin "P$54") (pinfunction "P$54_P$54") (pintype "bidirectional"))
    )
    (net (code "103") (name "unconnected-(U$1-PadP$58)") (class "Default")
      (node (ref "U$1") (pin "P$58") (pinfunction "P$58_P$58") (pintype "bidirectional"))
    )
    (net (code "104") (name "unconnected-(U$1-PadP$60)") (class "Default")
      (node (ref "U$1") (pin "P$60") (pinfunction "P$60_P$60") (pintype "bidirectional"))
    )
    (net (code "105") (name "unconnected-(U$1-PadP$61)") (class "Default")
      (node (ref "U$1") (pin "P$61") (pinfunction "P$61_P$61") (pintype "bidirectional"))
    )
    (net (code "106") (name "unconnected-(U$1-PadP$62)") (class "Default")
      (node (ref "U$1") (pin "P$62") (pinfunction "P$62_P$62") (pintype "bidirectional"))
    )
    (net (code "107") (name "unconnected-(U$1-PadP$63)") (class "Default")
      (node (ref "U$1") (pin "P$63") (pinfunction "P$63_P$63") (pintype "bidirectional"))
    )
    (net (code "108") (name "unconnected-(U$1-PadP$64)") (class "Default")
      (node (ref "U$1") (pin "P$64") (pinfunction "P$64_P$64") (pintype "bidirectional"))
    )
    (net (code "109") (name "unconnected-(U$1-PadP$65)") (class "Default")
      (node (ref "U$1") (pin "P$65") (pinfunction "P$65_P$65") (pintype "bidirectional"))
    )
    (net (code "110") (name "unconnected-(U$1-PadP$66)") (class "Default")
      (node (ref "U$1") (pin "P$66") (pinfunction "P$66_P$66") (pintype "bidirectional"))
    )
    (net (code "111") (name "unconnected-(U$1-PadP$67)") (class "Default")
      (node (ref "U$1") (pin "P$67") (pinfunction "P$67_P$67") (pintype "bidirectional"))
    )
    (net (code "112") (name "unconnected-(U$1-PadP$68)") (class "Default")
      (node (ref "U$1") (pin "P$68") (pinfunction "P$68_P$68") (pintype "bidirectional"))
    )
    (net (code "113") (name "unconnected-(U$1-PadP$73)") (class "Default")
      (node (ref "U$1") (pin "P$73") (pinfunction "P$73_P$73") (pintype "bidirectional"))
    )
    (net (code "114") (name "unconnected-(U$1-PadP$74)") (class "Default")
      (node (ref "U$1") (pin "P$74") (pinfunction "P$74_P$74") (pintype "bidirectional"))
    )
    (net (code "115") (name "unconnected-(U$1-PadP$75)") (class "Default")
      (node (ref "U$1") (pin "P$75") (pinfunction "P$75_P$75") (pintype "bidirectional"))
    )
    (net (code "116") (name "unconnected-(U$1-PadP$76)") (class "Default")
      (node (ref "U$1") (pin "P$76") (pinfunction "P$76_P$76") (pintype "bidirectional"))
    )
    (net (code "117") (name "unconnected-(U$1-PadP$81)") (class "Default")
      (node (ref "U$1") (pin "P$81") (pinfunction "P$81_P$81") (pintype "bidirectional"))
    )
    (net (code "118") (name "unconnected-(U$1-PadP$82)") (class "Default")
      (node (ref "U$1") (pin "P$82") (pinfunction "P$82_P$82") (pintype "bidirectional"))
    )
    (net (code "119") (name "unconnected-(U$1-PadP$83)") (class "Default")
      (node (ref "U$1") (pin "P$83") (pinfunction "P$83_P$83") (pintype "bidirectional"))
    )
    (net (code "120") (name "unconnected-(U$1-PadP$84)") (class "Default")
      (node (ref "U$1") (pin "P$84") (pinfunction "P$84_P$84") (pintype "bidirectional"))
    )
    (net (code "121") (name "unconnected-(U$1-PadP$89)") (class "Default")
      (node (ref "U$1") (pin "P$89") (pinfunction "P$89_P$89") (pintype "bidirectional"))
    )
    (net (code "122") (name "unconnected-(U$1-PadP$90)") (class "Default")
      (node (ref "U$1") (pin "P$90") (pinfunction "P$90_P$90") (pintype "bidirectional"))
    )
    (net (code "123") (name "unconnected-(U$1-PadP$91)") (class "Default")
      (node (ref "U$1") (pin "P$91") (pinfunction "P$91_P$91") (pintype "bidirectional"))
    )
    (net (code "124") (name "unconnected-(U$1-PadP$92)") (class "Default")
      (node (ref "U$1") (pin "P$92") (pinfunction "P$92_P$92") (pintype "bidirectional"))
    )
    (net (code "125") (name "unconnected-(U$1-PadP$95)") (class "Default")
      (node (ref "U$1") (pin "P$95") (pinfunction "P$95_P$95") (pintype "bidirectional"))
    )
    (net (code "126") (name "unconnected-(U$1-PadP$96)") (class "Default")
      (node (ref "U$1") (pin "P$96") (pinfunction "P$96_P$96") (pintype "bidirectional"))
    )
    (net (code "127") (name "unconnected-(U$1-RAHS_GND-PadP$94)") (class "Default")
      (node (ref "U$1") (pin "P$94") (pinfunction "RAHS_GND_P$94") (pintype "bidirectional"))
    )
    (net (code "128") (name "unconnected-(U$1-RAHS_VBAT-PadP$93)") (class "Default")
      (node (ref "U$1") (pin "P$93") (pinfunction "RAHS_VBAT_P$93") (pintype "bidirectional"))
    )
    (net (code "129") (name "unconnected-(U$1-SYNC1-PadP$45)") (class "Default")
      (node (ref "U$1") (pin "P$45") (pinfunction "SYNC1_P$45") (pintype "bidirectional"))
    )
    (net (code "130") (name "unconnected-(U$1-SYNC2-PadP$49)") (class "Default")
      (node (ref "U$1") (pin "P$49") (pinfunction "SYNC2_P$49") (pintype "bidirectional"))
    )
    (net (code "131") (name "unconnected-(U$1-TOPDEPLOY+-PadP$51)") (class "Default")
      (node (ref "U$1") (pin "P$51") (pinfunction "TOPDEPLOY+_P$51") (pintype "bidirectional"))
    )
    (net (code "132") (name "unconnected-(U$1-TOPDEPLOY+-PadP$55)") (class "Default")
      (node (ref "U$1") (pin "P$55") (pinfunction "TOPDEPLOY+_P$55") (pintype "bidirectional"))
    )
    (net (code "133") (name "unconnected-(U$1-TOPDEPLOY-$52-PadP$52)") (class "Default")
      (node (ref "U$1") (pin "P$52") (pinfunction "TOPDEPLOY-$52_P$52") (pintype "bidirectional"))
    )
    (net (code "134") (name "unconnected-(U$1-TOPDEPLOY-$56-PadP$56)") (class "Default")
      (node (ref "U$1") (pin "P$56") (pinfunction "TOPDEPLOY-$56_P$56") (pintype "bidirectional"))
    )
    (net (code "135") (name "unconnected-(U$1-WHEEL_GND-PadP$71)") (class "Default")
      (node (ref "U$1") (pin "P$71") (pinfunction "WHEEL_GND_P$71") (pintype "bidirectional"))
    )
    (net (code "136") (name "unconnected-(U$1-WHEEL_GND-PadP$72)") (class "Default")
      (node (ref "U$1") (pin "P$72") (pinfunction "WHEEL_GND_P$72") (pintype "bidirectional"))
    )
    (net (code "137") (name "unconnected-(U$1-WHEEL_VBAT-PadP$69)") (class "Default")
      (node (ref "U$1") (pin "P$69") (pinfunction "WHEEL_VBAT_P$69") (pintype "bidirectional"))
    )
    (net (code "138") (name "unconnected-(U$1-WHEEL_VBAT-PadP$70)") (class "Default")
      (node (ref "U$1") (pin "P$70") (pinfunction "WHEEL_VBAT_P$70") (pintype "bidirectional"))
    )
    (net (code "139") (name "unconnected-(U$7-P2.3_SPI-CS2-PadP2.4_SPI-CS2)") (class "Default")
      (node (ref "U$7") (pin "P2.4_SPI-CS2") (pinfunction "P2.3_SPI-CS2_P2.4_SPI-CS2") (pintype "bidirectional"))
    )
    (net (code "140") (name "unconnected-(U$7-PadP1.0_A0)") (class "Default")
      (node (ref "U$7") (pin "P1.0_A0") (pinfunction "P1.0_A0_P1.0_A0") (pintype "bidirectional"))
    )
    (net (code "141") (name "unconnected-(U$7-PadP1.1_A1)") (class "Default")
      (node (ref "U$7") (pin "P1.1_A1") (pinfunction "P1.1_A1_P1.1_A1") (pintype "bidirectional"))
    )
    (net (code "142") (name "unconnected-(U$7-PadP1.2_A2)") (class "Default")
      (node (ref "U$7") (pin "P1.2_A2") (pinfunction "P1.2_A2_P1.2_A2") (pintype "bidirectional"))
    )
    (net (code "143") (name "unconnected-(U$7-PadP1.3_A3)") (class "Default")
      (node (ref "U$7") (pin "P1.3_A3") (pinfunction "P1.3_A3_P1.3_A3") (pintype "bidirectional"))
    )
    (net (code "144") (name "unconnected-(U$7-PadP1.4_A4)") (class "Default")
      (node (ref "U$7") (pin "P1.4_A4") (pinfunction "P1.4_A4_P1.4_A4") (pintype "bidirectional"))
    )
    (net (code "145") (name "unconnected-(U$7-PadP1.5_A5)") (class "Default")
      (node (ref "U$7") (pin "P1.5_A5") (pinfunction "P1.5_A5_P1.5_A5") (pintype "bidirectional"))
    )
    (net (code "146") (name "unconnected-(U$7-PadP2.5_GPIO)") (class "Default")
      (node (ref "U$7") (pin "P2.5_GPIO") (pinfunction "P2.5_GPIO_P2.5_GPIO") (pintype "bidirectional"))
    )
    (net (code "147") (name "unconnected-(U$7-PadP2.7_SPI-CS3)") (class "Default")
      (node (ref "U$7") (pin "P2.7_SPI-CS3") (pinfunction "P2.7_SPI-CS3_P2.7_SPI-CS3") (pintype "bidirectional"))
    )
    (net (code "148") (name "unconnected-(U$7-PadP3.0_A12)") (class "Default")
      (node (ref "U$7") (pin "P3.0_A12") (pinfunction "P3.0_A12_P3.0_A12") (pintype "bidirectional"))
    )
    (net (code "149") (name "unconnected-(U$7-PadP3.1_A13)") (class "Default")
      (node (ref "U$7") (pin "P3.1_A13") (pinfunction "P3.1_A13_P3.1_A13") (pintype "bidirectional"))
    )
    (net (code "150") (name "unconnected-(U$7-PadP3.2_A14)") (class "Default")
      (node (ref "U$7") (pin "P3.2_A14") (pinfunction "P3.2_A14_P3.2_A14") (pintype "bidirectional"))
    )
    (net (code "151") (name "unconnected-(U$7-PadP3.3_A15)") (class "Default")
      (node (ref "U$7") (pin "P3.3_A15") (pinfunction "P3.3_A15_P3.3_A15") (pintype "bidirectional"))
    )
    (net (code "152") (name "unconnected-(U$7-PadP4.0_GPIO)") (class "Default")
      (node (ref "U$7") (pin "P4.0_GPIO") (pinfunction "P4.0_GPIO_P4.0_GPIO") (pintype "bidirectional"))
    )
    (net (code "153") (name "unconnected-(U$7-PadP4.1_GPIO)") (class "Default")
      (node (ref "U$7") (pin "P4.1_GPIO") (pinfunction "P4.1_GPIO_P4.1_GPIO") (pintype "bidirectional"))
    )
    (net (code "154") (name "unconnected-(U$7-PadP4.2_GPIO)") (class "Default")
      (node (ref "U$7") (pin "P4.2_GPIO") (pinfunction "P4.2_GPIO_P4.2_GPIO") (pintype "bidirectional"))
    )
    (net (code "155") (name "unconnected-(U$7-PadP4.3_GPIO)") (class "Default")
      (node (ref "U$7") (pin "P4.3_GPIO") (pinfunction "P4.3_GPIO_P4.3_GPIO") (pintype "bidirectional"))
    )
    (net (code "156") (name "unconnected-(U$7-PadP5.0_I2C-SDA-1)") (class "Default")
      (node (ref "U$7") (pin "P5.0_I2C-SDA-1") (pinfunction "P5.0_I2C-SDA-1_P5.0_I2C-SDA-1") (pintype "bidirectional"))
    )
    (net (code "157") (name "unconnected-(U$7-PadP5.1_I2C-SCL-1)") (class "Default")
      (node (ref "U$7") (pin "P5.1_I2C-SCL-1") (pinfunction "P5.1_I2C-SCL-1_P5.1_I2C-SCL-1") (pintype "bidirectional"))
    )
    (net (code "158") (name "unconnected-(U$7-PadP5.4_SPI-MOSI)") (class "Default")
      (node (ref "U$7") (pin "P5.4_SPI-MOSI") (pinfunction "P5.4_SPI-MOSI_P5.4_SPI-MOSI") (pintype "bidirectional"))
    )
    (net (code "159") (name "unconnected-(U$7-PadP5.5_SPI-MISO)") (class "Default")
      (node (ref "U$7") (pin "P5.5_SPI-MISO") (pinfunction "P5.5_SPI-MISO_P5.5_SPI-MISO") (pintype "bidirectional"))
    )
    (net (code "160") (name "unconnected-(U$7-PadP5.6_SPI-CLK)") (class "Default")
      (node (ref "U$7") (pin "P5.6_SPI-CLK") (pinfunction "P5.6_SPI-CLK_P5.6_SPI-CLK") (pintype "bidirectional"))
    )
    (net (code "161") (name "unconnected-(U$7-PadP7.0_I2C-SDA-2)") (class "Default")
      (node (ref "U$7") (pin "P7.0_I2C-SDA-2") (pinfunction "P7.0_I2C-SDA-2_P7.0_I2C-SDA-2") (pintype "bidirectional"))
    )
    (net (code "162") (name "unconnected-(U$7-PadP7.1_I2C-SCL-2)") (class "Default")
      (node (ref "U$7") (pin "P7.1_I2C-SCL-2") (pinfunction "P7.1_I2C-SCL-2_P7.1_I2C-SCL-2") (pintype "bidirectional"))
    )
    (net (code "163") (name "unconnected-(U$7-PadP7.2_SYNC1)") (class "Default")
      (node (ref "U$7") (pin "P7.2_SYNC1") (pinfunction "P7.2_SYNC1_P7.2_SYNC1") (pintype "bidirectional"))
    )
    (net (code "164") (name "unconnected-(U$7-PadP7.3_GPIO)") (class "Default")
      (node (ref "U$7") (pin "P7.3_GPIO") (pinfunction "P7.3_GPIO_P7.3_GPIO") (pintype "bidirectional"))
    )
    (net (code "165") (name "unconnected-(U$7-PadP7.4_GPIO)") (class "Default")
      (node (ref "U$7") (pin "P7.4_GPIO") (pinfunction "P7.4_GPIO_P7.4_GPIO") (pintype "bidirectional"))
    )
    (net (code "166") (name "unconnected-(U$7-PadPJ.3_SYNC2)") (class "Default")
      (node (ref "U$7") (pin "PJ.3_SYNC2") (pinfunction "PJ.3_SYNC2_PJ.3_SYNC2") (pintype "bidirectional"))
    )
  )
)
